# lptim_encoder.net
KiCad netlist of a schematic drawn in EAGLE
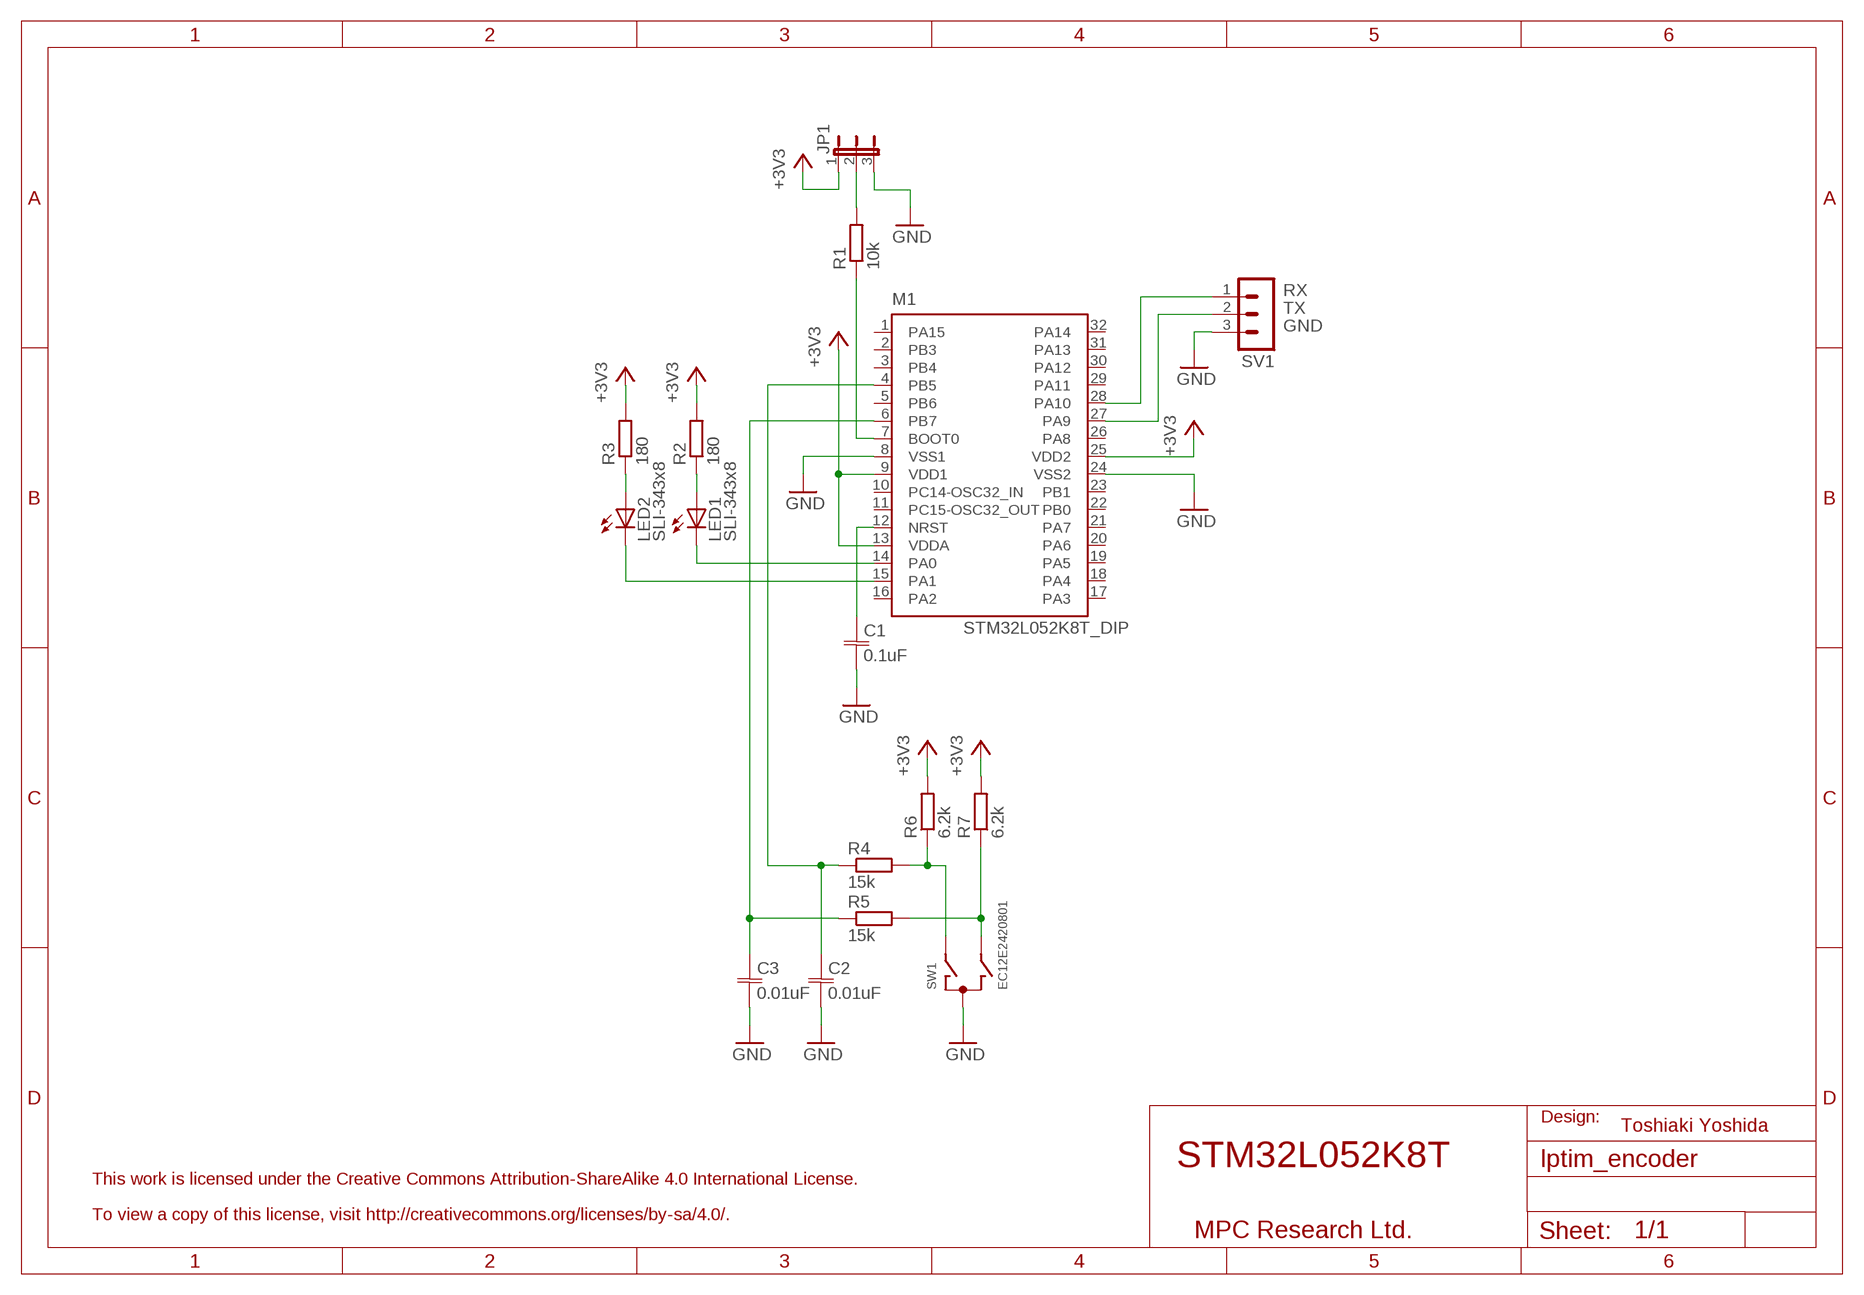
[diagram p0: schematic, sheet 1]

(export (version "E")
  (design (tool "Eeschema 10.0.6"))
  (components
    (comp (ref "C1")
      (value "0.1uF")
      (footprint "eagle-import:C050-024X044")
      (libsource (lib "eagle-import") (part "C-JIS050-024X044"))
    )
    (comp (ref "C2")
      (value "0.01uF")
      (footprint "eagle-import:C050-024X044")
      (libsource (lib "eagle-import") (part "C-JIS050-024X044"))
    )
    (comp (ref "C3")
      (value "0.01uF")
      (footprint "eagle-import:C050-024X044")
      (libsource (lib "eagle-import") (part "C-JIS050-024X044"))
    )
    (comp (ref "JP1")
      (value "JP2E")
      (footprint "eagle-import:JP2")
      (libsource (lib "eagle-import") (part "JP2E"))
    )
    (comp (ref "LED1")
      (value "SLI-343x8")
      (footprint "eagle-import:LED3MM")
      (libsource (lib "eagle-import") (part "LED3MM"))
    )
    (comp (ref "LED2")
      (value "SLI-343x8")
      (footprint "eagle-import:LED3MM")
      (libsource (lib "eagle-import") (part "LED3MM"))
    )
    (comp (ref "M1")
      (value "STM32L052K8T_DIP")
      (footprint "eagle-import:DIP32")
      (libsource (lib "eagle-import") (part "STM32L052K8T_DIP"))
    )
    (comp (ref "R1")
      (value "10k")
      (footprint "eagle-import:0207_2V")
      (libsource (lib "eagle-import") (part "R-EU_0207/2V"))
    )
    (comp (ref "R2")
      (value "180")
      (footprint "eagle-import:0207_2V")
      (libsource (lib "eagle-import") (part "R-EU_0207/2V"))
    )
    (comp (ref "R3")
      (value "180")
      (footprint "eagle-import:0207_2V")
      (libsource (lib "eagle-import") (part "R-EU_0207/2V"))
    )
    (comp (ref "R4")
      (value "15k")
      (footprint "eagle-import:0207_2V")
      (libsource (lib "eagle-import") (part "R-EU_0207/2V"))
    )
    (comp (ref "R5")
      (value "15k")
      (footprint "eagle-import:0207_2V")
      (libsource (lib "eagle-import") (part "R-EU_0207/2V"))
    )
    (comp (ref "R6")
      (value "6.2k")
      (footprint "eagle-import:0207_2V")
      (libsource (lib "eagle-import") (part "R-EU_0207/2V"))
    )
    (comp (ref "R7")
      (value "6.2k")
      (footprint "eagle-import:0207_2V")
      (libsource (lib "eagle-import") (part "R-EU_0207/2V"))
    )
    (comp (ref "SV1")
      (value "MA03-1")
      (footprint "eagle-import:MA03-1")
      (libsource (lib "eagle-import") (part "MA03-1"))
    )
    (comp (ref "SW1")
      (value "EC12E2420801")
      (footprint "eagle-import:ALPS_EC12E_SW")
      (fields (field (name "MPN") "EC12E2424407"))
      (libsource (lib "eagle-import") (part "EC12E_SW"))
    )
  )
  (nets
    (net (code "1") (name "+3V3") (class "Default")
      (node (ref "JP1") (pin "1") (pinfunction "1_1") (pintype "passive"))
      (node (ref "M1") (pin "13") (pinfunction "VDDA_13") (pintype "power_in"))
      (node (ref "M1") (pin "25") (pinfunction "VDD2_25") (pintype "bidirectional"))
      (node (ref "M1") (pin "9") (pinfunction "VDD1_9") (pintype "power_in"))
      (node (ref "R2") (pin "2") (pinfunction "2_2") (pintype "passive"))
      (node (ref "R3") (pin "2") (pinfunction "2_2") (pintype "passive"))
      (node (ref "R6") (pin "2") (pinfunction "2_2") (pintype "passive"))
      (node (ref "R7") (pin "2") (pinfunction "2_2") (pintype "passive"))
    )
    (net (code "2") (name "GND") (class "Default")
      (node (ref "C1") (pin "2") (pinfunction "2_2") (pintype "passive"))
      (node (ref "C2") (pin "2") (pinfunction "2_2") (pintype "passive"))
      (node (ref "C3") (pin "2") (pinfunction "2_2") (pintype "passive"))
      (node (ref "JP1") (pin "3") (pinfunction "3_3") (pintype "passive"))
      (node (ref "M1") (pin "24") (pinfunction "VSS2_24") (pintype "power_in"))
      (node (ref "M1") (pin "8") (pinfunction "VSS1_8") (pintype "power_in"))
      (node (ref "SV1") (pin "3") (pinfunction "3_3") (pintype "passive"))
      (node (ref "SW1") (pin "C") (pinfunction "C_C") (pintype "passive"))
    )
    (net (code "3") (name "Net-(JP1-Pad2)") (class "Default")
      (node (ref "JP1") (pin "2") (pinfunction "2_2") (pintype "passive"))
      (node (ref "R1") (pin "2") (pinfunction "2_2") (pintype "passive"))
    )
    (net (code "4") (name "Net-(LED1-C)") (class "Default")
      (node (ref "LED1") (pin "K") (pinfunction "C_K") (pintype "passive"))
      (node (ref "M1") (pin "14") (pinfunction "PA0_14") (pintype "bidirectional"))
    )
    (net (code "5") (name "Net-(LED1-PadA)") (class "Default")
      (node (ref "LED1") (pin "A") (pinfunction "A_A") (pintype "passive"))
      (node (ref "R2") (pin "1") (pinfunction "1_1") (pintype "passive"))
    )
    (net (code "6") (name "Net-(LED2-C)") (class "Default")
      (node (ref "LED2") (pin "K") (pinfunction "C_K") (pintype "passive"))
      (node (ref "M1") (pin "15") (pinfunction "PA1_15") (pintype "bidirectional"))
    )
    (net (code "7") (name "Net-(LED2-PadA)") (class "Default")
      (node (ref "LED2") (pin "A") (pinfunction "A_A") (pintype "passive"))
      (node (ref "R3") (pin "1") (pinfunction "1_1") (pintype "passive"))
    )
    (net (code "8") (name "Net-(M1-BOOT0)") (class "Default")
      (node (ref "M1") (pin "7") (pinfunction "BOOT0_7") (pintype "bidirectional"))
      (node (ref "R1") (pin "1") (pinfunction "1_1") (pintype "passive"))
    )
    (net (code "9") (name "Net-(M1-NRST)") (class "Default")
      (node (ref "C1") (pin "1") (pinfunction "1_1") (pintype "passive"))
      (node (ref "M1") (pin "12") (pinfunction "NRST_12") (pintype "bidirectional"))
    )
    (net (code "10") (name "Net-(M1-PA9)") (class "Default")
      (node (ref "M1") (pin "27") (pinfunction "PA9_27") (pintype "bidirectional"))
      (node (ref "SV1") (pin "2") (pinfunction "2_2") (pintype "passive"))
    )
    (net (code "11") (name "Net-(M1-PA10)") (class "Default")
      (node (ref "M1") (pin "28") (pinfunction "PA10_28") (pintype "bidirectional"))
      (node (ref "SV1") (pin "1") (pinfunction "1_1") (pintype "passive"))
    )
    (net (code "12") (name "Net-(M1-PB5)") (class "Default")
      (node (ref "C2") (pin "1") (pinfunction "1_1") (pintype "passive"))
      (node (ref "M1") (pin "4") (pinfunction "PB5_4") (pintype "bidirectional"))
      (node (ref "R4") (pin "1") (pinfunction "1_1") (pintype "passive"))
    )
    (net (code "13") (name "Net-(M1-PB7)") (class "Default")
      (node (ref "C3") (pin "1") (pinfunction "1_1") (pintype "passive"))
      (node (ref "M1") (pin "6") (pinfunction "PB7_6") (pintype "bidirectional"))
      (node (ref "R5") (pin "1") (pinfunction "1_1") (pintype "passive"))
    )
    (net (code "14") (name "Net-(R4-Pad2)") (class "Default")
      (node (ref "R4") (pin "2") (pinfunction "2_2") (pintype "passive"))
      (node (ref "R6") (pin "1") (pinfunction "1_1") (pintype "passive"))
      (node (ref "SW1") (pin "A") (pinfunction "A_A") (pintype "passive"))
    )
    (net (code "15") (name "Net-(R5-Pad2)") (class "Default")
      (node (ref "R5") (pin "2") (pinfunction "2_2") (pintype "passive"))
      (node (ref "R7") (pin "1") (pinfunction "1_1") (pintype "passive"))
      (node (ref "SW1") (pin "B") (pinfunction "B_B") (pintype "passive"))
    )
    (net (code "16") (name "unconnected-(M1-PA2-Pad16)") (class "Default")
      (node (ref "M1") (pin "16") (pinfunction "PA2_16") (pintype "bidirectional"))
    )
    (net (code "17") (name "unconnected-(M1-PA3-Pad17)") (class "Default")
      (node (ref "M1") (pin "17") (pinfunction "PA3_17") (pintype "bidirectional"))
    )
    (net (code "18") (name "unconnected-(M1-PA4-Pad18)") (class "Default")
      (node (ref "M1") (pin "18") (pinfunction "PA4_18") (pintype "bidirectional"))
    )
    (net (code "19") (name "unconnected-(M1-PA5-Pad19)") (class "Default")
      (node (ref "M1") (pin "19") (pinfunction "PA5_19") (pintype "bidirectional"))
    )
    (net (code "20") (name "unconnected-(M1-PA6-Pad20)") (class "Default")
      (node (ref "M1") (pin "20") (pinfunction "PA6_20") (pintype "bidirectional"))
    )
    (net (code "21") (name "unconnected-(M1-PA7-Pad21)") (class "Default")
      (node (ref "M1") (pin "21") (pinfunction "PA7_21") (pintype "bidirectional"))
    )
    (net (code "22") (name "unconnected-(M1-PA8-Pad26)") (class "Default")
      (node (ref "M1") (pin "26") (pinfunction "PA8_26") (pintype "bidirectional"))
    )
    (net (code "23") (name "unconnected-(M1-PA11-Pad29)") (class "Default")
      (node (ref "M1") (pin "29") (pinfunction "PA11_29") (pintype "bidirectional"))
    )
    (net (code "24") (name "unconnected-(M1-PA12-Pad30)") (class "Default")
      (node (ref "M1") (pin "30") (pinfunction "PA12_30") (pintype "bidirectional"))
    )
    (net (code "25") (name "unconnected-(M1-PA13-Pad31)") (class "Default")
      (node (ref "M1") (pin "31") (pinfunction "PA13_31") (pintype "bidirectional"))
    )
    (net (code "26") (name "unconnected-(M1-PA14-Pad32)") (class "Default")
      (node (ref "M1") (pin "32") (pinfunction "PA14_32") (pintype "bidirectional"))
    )
    (net (code "27") (name "unconnected-(M1-PA15-Pad1)") (class "Default")
      (node (ref "M1") (pin "1") (pinfunction "PA15_1") (pintype "bidirectional"))
    )
    (net (code "28") (name "unconnected-(M1-PB0-Pad22)") (class "Default")
      (node (ref "M1") (pin "22") (pinfunction "PB0_22") (pintype "bidirectional"))
    )
    (net (code "29") (name "unconnected-(M1-PB1-Pad23)") (class "Default")
      (node (ref "M1") (pin "23") (pinfunction "PB1_23") (pintype "bidirectional"))
    )
    (net (code "30") (name "unconnected-(M1-PB3-Pad2)") (class "Default")
      (node (ref "M1") (pin "2") (pinfunction "PB3_2") (pintype "bidirectional"))
    )
    (net (code "31") (name "unconnected-(M1-PB4-Pad3)") (class "Default")
      (node (ref "M1") (pin "3") (pinfunction "PB4_3") (pintype "bidirectional"))
    )
    (net (code "32") (name "unconnected-(M1-PB6-Pad5)") (class "Default")
      (node (ref "M1") (pin "5") (pinfunction "PB6_5") (pintype "bidirectional"))
    )
    (net (code "33") (name "unconnected-(M1-PC14-OSC32_IN-Pad10)") (class "Default")
      (node (ref "M1") (pin "10") (pinfunction "PC14-OSC32_IN_10") (pintype "bidirectional"))
    )
    (net (code "34") (name "unconnected-(M1-PC15-OSC32_OUT-Pad11)") (class "Default")
      (node (ref "M1") (pin "11") (pinfunction "PC15-OSC32_OUT_11") (pintype "bidirectional"))
    )
  )
)
